# Musicbox.net
KiCad netlist of a schematic drawn in EAGLE
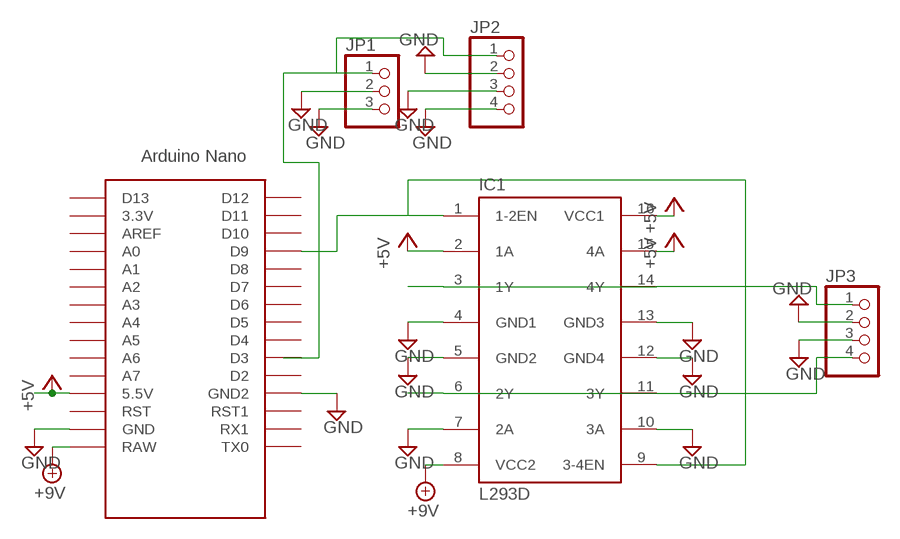
[diagram p0: schematic, sheet 1]

(export (version "E")
  (design (tool "Eeschema 10.0.6"))
  (components
    (comp (ref "IC1")
      (value "L293D")
      (footprint "eagle-import:DIL16")
      (libsource (lib "eagle-import") (part "L293D"))
    )
    (comp (ref "JP1")
      (value "PINHD-1X3")
      (footprint "eagle-import:1X03")
      (libsource (lib "eagle-import") (part "PINHD-1X3"))
    )
    (comp (ref "JP2")
      (value "PINHD-1X4")
      (footprint "eagle-import:1X04")
      (libsource (lib "eagle-import") (part "PINHD-1X4"))
    )
    (comp (ref "JP3")
      (value "PINHD-1X4")
      (footprint "eagle-import:1X04")
      (libsource (lib "eagle-import") (part "PINHD-1X4"))
    )
    (comp (ref "U$1")
      (value "NANO")
      (footprint "eagle-import:NANO")
      (libsource (lib "eagle-import") (part "NANO"))
    )
  )
  (nets
    (net (code "1") (name "+5V") (class "Default")
      (node (ref "IC1") (pin "15") (pinfunction "4A_15") (pintype "input"))
      (node (ref "IC1") (pin "16") (pinfunction "VCC1_16") (pintype "power_in"))
      (node (ref "IC1") (pin "2") (pinfunction "1A_2") (pintype "input"))
      (node (ref "U$1") (pin "5V") (pinfunction "5.5V_5V") (pintype "bidirectional"))
    )
    (net (code "2") (name "+9V") (class "Default")
      (node (ref "IC1") (pin "8") (pinfunction "VCC2_8") (pintype "power_in"))
      (node (ref "U$1") (pin "RAW") (pinfunction "RAW_RAW") (pintype "bidirectional"))
    )
    (net (code "3") (name "GND") (class "Default")
      (node (ref "IC1") (pin "10") (pinfunction "3A_10") (pintype "input"))
      (node (ref "IC1") (pin "12") (pinfunction "GND4_12") (pintype "power_in"))
      (node (ref "IC1") (pin "13") (pinfunction "GND3_13") (pintype "power_in"))
      (node (ref "IC1") (pin "4") (pinfunction "GND1_4") (pintype "power_in"))
      (node (ref "IC1") (pin "5") (pinfunction "GND2_5") (pintype "power_in"))
      (node (ref "IC1") (pin "7") (pinfunction "2A_7") (pintype "input"))
      (node (ref "JP1") (pin "2") (pinfunction "2_2") (pintype "passive"))
      (node (ref "JP1") (pin "3") (pinfunction "3_3") (pintype "passive"))
      (node (ref "JP2") (pin "2") (pinfunction "2_2") (pintype "passive"))
      (node (ref "JP2") (pin "3") (pinfunction "3_3") (pintype "passive"))
      (node (ref "JP2") (pin "4") (pinfunction "4_4") (pintype "passive"))
      (node (ref "JP3") (pin "2") (pinfunction "2_2") (pintype "passive"))
      (node (ref "JP3") (pin "3") (pinfunction "3_3") (pintype "passive"))
      (node (ref "U$1") (pin "GND") (pinfunction "GND_GND") (pintype "bidirectional"))
      (node (ref "U$1") (pin "GND1") (pinfunction "GND2_GND1") (pintype "bidirectional"))
    )
    (net (code "4") (name "Net-(IC1-1-2EN)") (class "Default")
      (node (ref "IC1") (pin "1") (pinfunction "1-2EN_1") (pintype "input"))
      (node (ref "IC1") (pin "9") (pinfunction "3-4EN_9") (pintype "input"))
      (node (ref "U$1") (pin "D9") (pinfunction "D9_D9") (pintype "bidirectional"))
    )
    (net (code "5") (name "Net-(IC1-1Y)") (class "Default")
      (node (ref "IC1") (pin "14") (pinfunction "4Y_14") (pintype "output"))
      (node (ref "IC1") (pin "3") (pinfunction "1Y_3") (pintype "output"))
      (node (ref "JP3") (pin "1") (pinfunction "1_1") (pintype "passive"))
    )
    (net (code "6") (name "Net-(IC1-2Y)") (class "Default")
      (node (ref "IC1") (pin "11") (pinfunction "3Y_11") (pintype "output"))
      (node (ref "IC1") (pin "6") (pinfunction "2Y_6") (pintype "output"))
      (node (ref "JP3") (pin "4") (pinfunction "4_4") (pintype "passive"))
    )
    (net (code "7") (name "Net-(JP1-Pad1)") (class "Default")
      (node (ref "JP1") (pin "1") (pinfunction "1_1") (pintype "passive"))
      (node (ref "JP2") (pin "1") (pinfunction "1_1") (pintype "passive"))
      (node (ref "U$1") (pin "D3") (pinfunction "D3_D3") (pintype "bidirectional"))
    )
    (net (code "8") (name "unconnected-(U$1-Pad3.3V)") (class "Default")
      (node (ref "U$1") (pin "3.3V") (pinfunction "3.3V_3.3V") (pintype "bidirectional"))
    )
    (net (code "9") (name "unconnected-(U$1-PadA0)") (class "Default")
      (node (ref "U$1") (pin "A0") (pinfunction "A0_A0") (pintype "bidirectional"))
    )
    (net (code "10") (name "unconnected-(U$1-PadA1)") (class "Default")
      (node (ref "U$1") (pin "A1") (pinfunction "A1_A1") (pintype "bidirectional"))
    )
    (net (code "11") (name "unconnected-(U$1-PadA2)") (class "Default")
      (node (ref "U$1") (pin "A2") (pinfunction "A2_A2") (pintype "bidirectional"))
    )
    (net (code "12") (name "unconnected-(U$1-PadA3)") (class "Default")
      (node (ref "U$1") (pin "A3") (pinfunction "A3_A3") (pintype "bidirectional"))
    )
    (net (code "13") (name "unconnected-(U$1-PadA4)") (class "Default")
      (node (ref "U$1") (pin "A4") (pinfunction "A4_A4") (pintype "bidirectional"))
    )
    (net (code "14") (name "unconnected-(U$1-PadA5)") (class "Default")
      (node (ref "U$1") (pin "A5") (pinfunction "A5_A5") (pintype "bidirectional"))
    )
    (net (code "15") (name "unconnected-(U$1-PadA6)") (class "Default")
      (node (ref "U$1") (pin "A6") (pinfunction "A6_A6") (pintype "bidirectional"))
    )
    (net (code "16") (name "unconnected-(U$1-PadA7)") (class "Default")
      (node (ref "U$1") (pin "A7") (pinfunction "A7_A7") (pintype "bidirectional"))
    )
    (net (code "17") (name "unconnected-(U$1-PadAREF)") (class "Default")
      (node (ref "U$1") (pin "AREF") (pinfunction "AREF_AREF") (pintype "bidirectional"))
    )
    (net (code "18") (name "unconnected-(U$1-PadD2)") (class "Default")
      (node (ref "U$1") (pin "D2") (pinfunction "D2_D2") (pintype "bidirectional"))
    )
    (net (code "19") (name "unconnected-(U$1-PadD4)") (class "Default")
      (node (ref "U$1") (pin "D4") (pinfunction "D4_D4") (pintype "bidirectional"))
    )
    (net (code "20") (name "unconnected-(U$1-PadD5)") (class "Default")
      (node (ref "U$1") (pin "D5") (pinfunction "D5_D5") (pintype "bidirectional"))
    )
    (net (code "21") (name "unconnected-(U$1-PadD6)") (class "Default")
      (node (ref "U$1") (pin "D6") (pinfunction "D6_D6") (pintype "bidirectional"))
    )
    (net (code "22") (name "unconnected-(U$1-PadD7)") (class "Default")
      (node (ref "U$1") (pin "D7") (pinfunction "D7_D7") (pintype "bidirectional"))
    )
    (net (code "23") (name "unconnected-(U$1-PadD8)") (class "Default")
      (node (ref "U$1") (pin "D8") (pinfunction "D8_D8") (pintype "bidirectional"))
    )
    (net (code "24") (name "unconnected-(U$1-PadD10)") (class "Default")
      (node (ref "U$1") (pin "D10") (pinfunction "D10_D10") (pintype "bidirectional"))
    )
    (net (code "25") (name "unconnected-(U$1-PadD11)") (class "Default")
      (node (ref "U$1") (pin "D11") (pinfunction "D11_D11") (pintype "bidirectional"))
    )
    (net (code "26") (name "unconnected-(U$1-PadD12)") (class "Default")
      (node (ref "U$1") (pin "D12") (pinfunction "D12_D12") (pintype "bidirectional"))
    )
    (net (code "27") (name "unconnected-(U$1-PadD13)") (class "Default")
      (node (ref "U$1") (pin "D13") (pinfunction "D13_D13") (pintype "bidirectional"))
    )
    (net (code "28") (name "unconnected-(U$1-PadICSP1)") (class "Default")
      (node (ref "U$1") (pin "ICSP1") (pinfunction "ICSP1_ICSP1") (pintype "bidirectional"))
    )
    (net (code "29") (name "unconnected-(U$1-PadICSP2)") (class "Default")
      (node (ref "U$1") (pin "ICSP2") (pinfunction "ICSP2_ICSP2") (pintype "bidirectional"))
    )
    (net (code "30") (name "unconnected-(U$1-PadICSP3)") (class "Default")
      (node (ref "U$1") (pin "ICSP3") (pinfunction "ICSP3_ICSP3") (pintype "bidirectional"))
    )
    (net (code "31") (name "unconnected-(U$1-PadICSP4)") (class "Default")
      (node (ref "U$1") (pin "ICSP4") (pinfunction "ICSP4_ICSP4") (pintype "bidirectional"))
    )
    (net (code "32") (name "unconnected-(U$1-PadICSP5)") (class "Default")
      (node (ref "U$1") (pin "ICSP5") (pinfunction "ICSP5_ICSP5") (pintype "bidirectional"))
    )
    (net (code "33") (name "unconnected-(U$1-PadICSP6)") (class "Default")
      (node (ref "U$1") (pin "ICSP6") (pinfunction "ICSP6_ICSP6") (pintype "bidirectional"))
    )
    (net (code "34") (name "unconnected-(U$1-PadRST)") (class "Default")
      (node (ref "U$1") (pin "RST") (pinfunction "RST_RST") (pintype "bidirectional"))
    )
    (net (code "35") (name "unconnected-(U$1-PadRST1)") (class "Default")
      (node (ref "U$1") (pin "RST1") (pinfunction "RST1_RST1") (pintype "bidirectional"))
    )
    (net (code "36") (name "unconnected-(U$1-PadRX1)") (class "Default")
      (node (ref "U$1") (pin "RX1") (pinfunction "RX1_RX1") (pintype "bidirectional"))
    )
    (net (code "37") (name "unconnected-(U$1-PadTX0)") (class "Default")
      (node (ref "U$1") (pin "TX0") (pinfunction "TX0_TX0") (pintype "bidirectional"))
    )
  )
)
